# Angelo_Dual_Filter_MAIN_v1.net
KiCad netlist of a schematic drawn in EAGLE
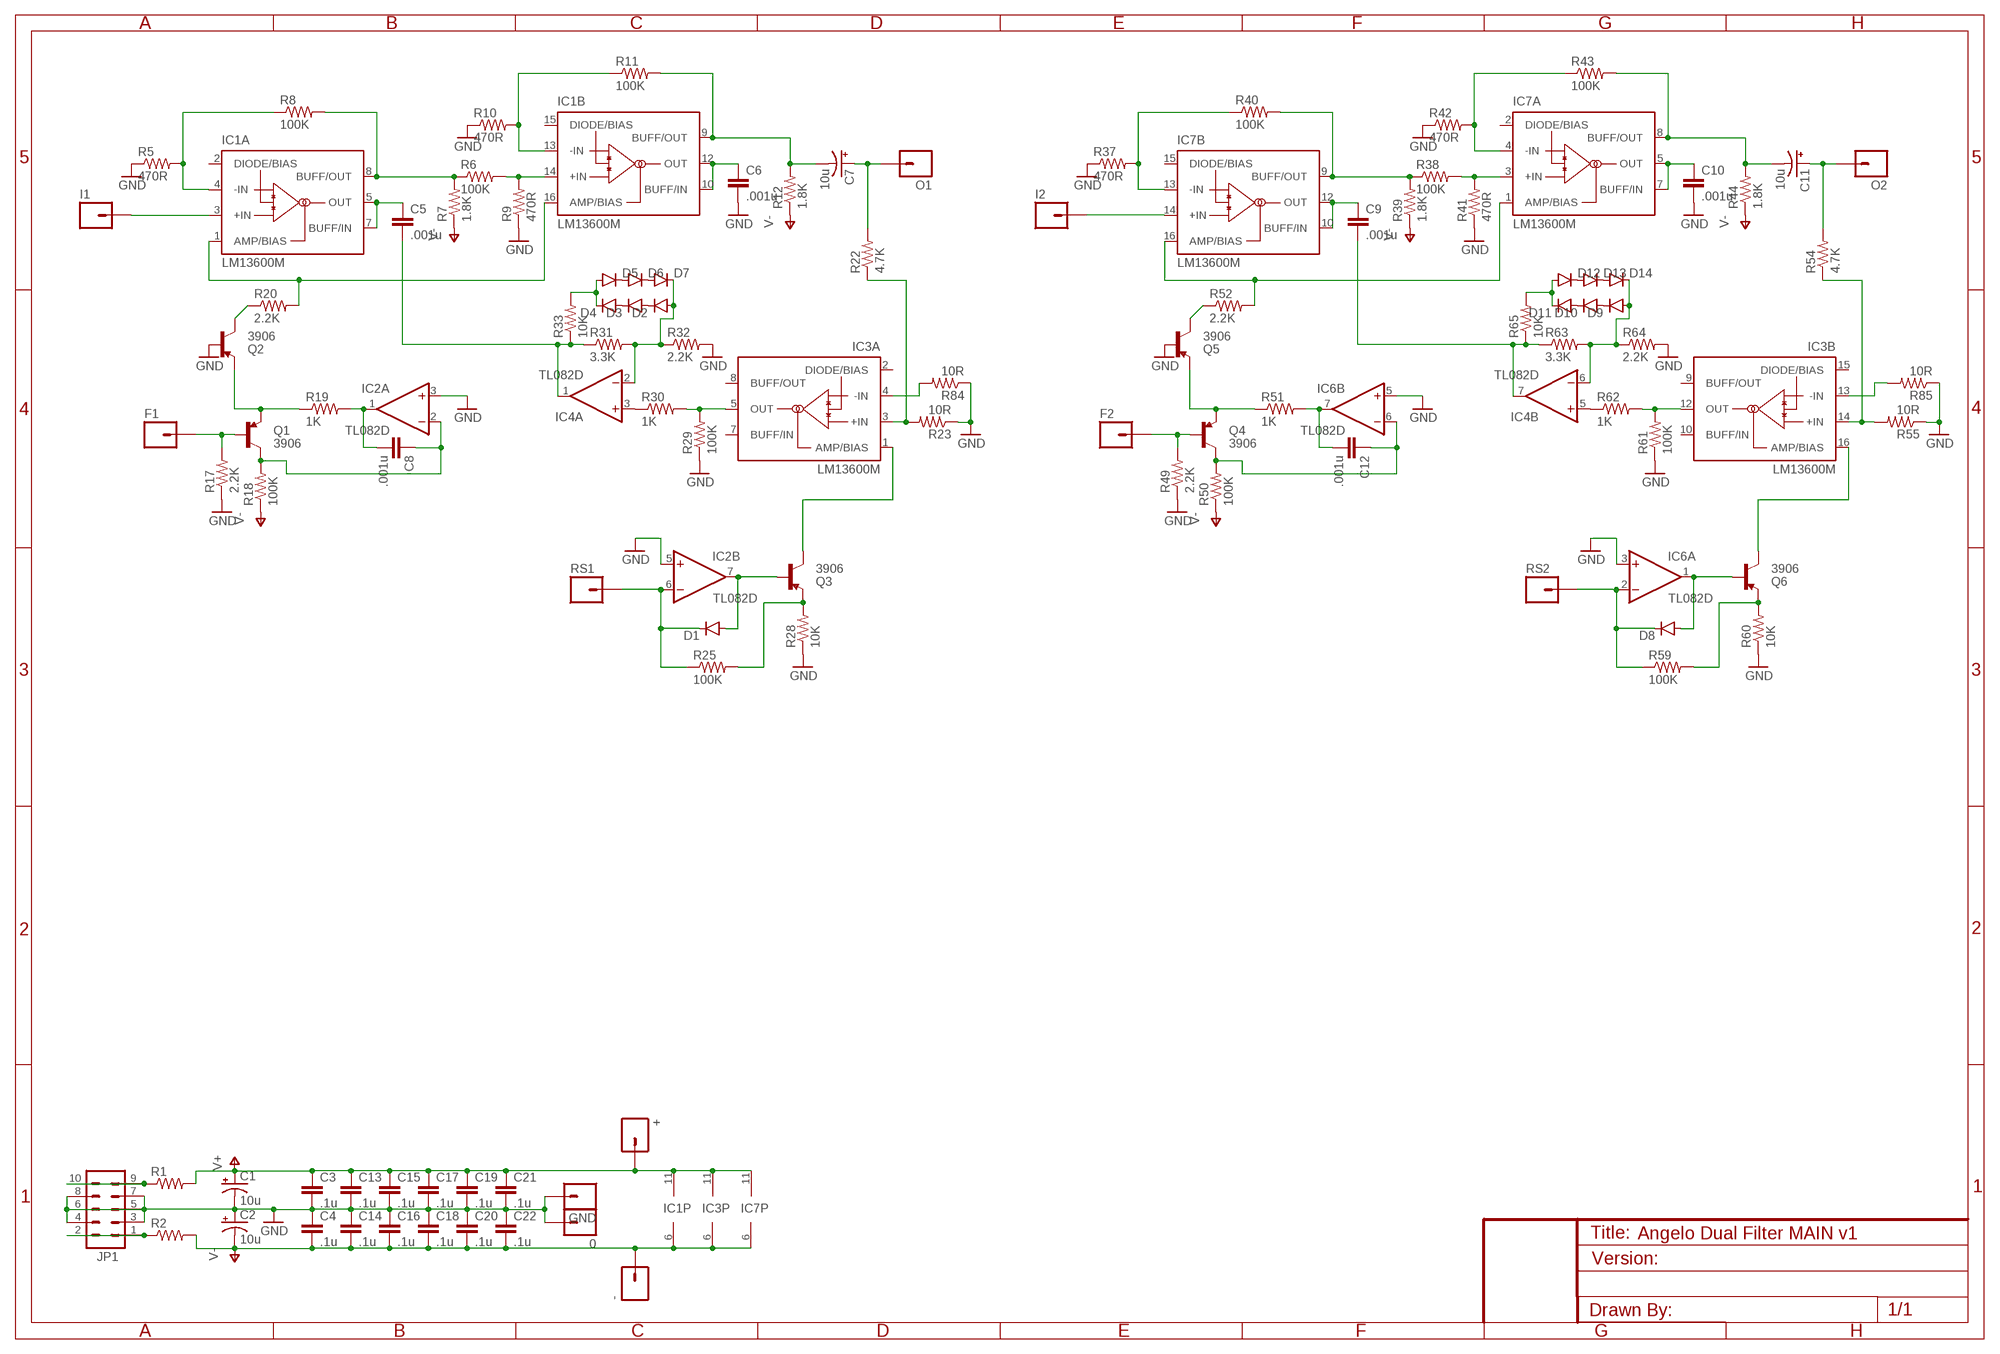
[diagram p0: schematic, sheet 1]

(export (version "E")
  (design (tool "Eeschema 10.0.6"))
  (components
    (comp (ref "+")
      (value "M01PTH")
      (footprint "eagle-import:1X01")
      (libsource (lib "eagle-import") (part "M01PTH"))
    )
    (comp (ref "-")
      (value "M01PTH")
      (footprint "eagle-import:1X01")
      (libsource (lib "eagle-import") (part "M01PTH"))
    )
    (comp (ref "0")
      (value "M01PTH")
      (footprint "eagle-import:1X01")
      (libsource (lib "eagle-import") (part "M01PTH"))
    )
    (comp (ref "C1")
      (value "10u")
      (footprint "eagle-import:CPOL-RADIAL-10UF-25V")
      (libsource (lib "eagle-import") (part "CAP_POLPTH2"))
    )
    (comp (ref "C2")
      (value "10u")
      (footprint "eagle-import:CPOL-RADIAL-10UF-25V")
      (libsource (lib "eagle-import") (part "CAP_POLPTH2"))
    )
    (comp (ref "C3")
      (value ".1u")
      (footprint "eagle-import:0805")
      (libsource (lib "eagle-import") (part "CAP0805"))
    )
    (comp (ref "C4")
      (value ".1u")
      (footprint "eagle-import:0805")
      (libsource (lib "eagle-import") (part "CAP0805"))
    )
    (comp (ref "C5")
      (value ".001u")
      (footprint "eagle-import:C5B2.5")
      (libsource (lib "eagle-import") (part "C5/2.5"))
    )
    (comp (ref "C6")
      (value ".001u")
      (footprint "eagle-import:C5B2.5")
      (libsource (lib "eagle-import") (part "C5/2.5"))
    )
    (comp (ref "C7")
      (value "10u")
      (footprint "eagle-import:CPOL-RADIAL-10UF-25V")
      (libsource (lib "eagle-import") (part "CAP_POLPTH2"))
    )
    (comp (ref "C8")
      (value ".001u")
      (footprint "eagle-import:0805")
      (libsource (lib "eagle-import") (part "CAP0805"))
    )
    (comp (ref "C9")
      (value ".001u")
      (footprint "eagle-import:C5B2.5")
      (libsource (lib "eagle-import") (part "C5/2.5"))
    )
    (comp (ref "C10")
      (value ".001u")
      (footprint "eagle-import:C5B2.5")
      (libsource (lib "eagle-import") (part "C5/2.5"))
    )
    (comp (ref "C11")
      (value "10u")
      (footprint "eagle-import:CPOL-RADIAL-10UF-25V")
      (libsource (lib "eagle-import") (part "CAP_POLPTH2"))
    )
    (comp (ref "C12")
      (value ".001u")
      (footprint "eagle-import:0805")
      (libsource (lib "eagle-import") (part "CAP0805"))
    )
    (comp (ref "C13")
      (value ".1u")
      (footprint "eagle-import:0805")
      (libsource (lib "eagle-import") (part "CAP0805"))
    )
    (comp (ref "C14")
      (value ".1u")
      (footprint "eagle-import:0805")
      (libsource (lib "eagle-import") (part "CAP0805"))
    )
    (comp (ref "C15")
      (value ".1u")
      (footprint "eagle-import:0805")
      (libsource (lib "eagle-import") (part "CAP0805"))
    )
    (comp (ref "C16")
      (value ".1u")
      (footprint "eagle-import:0805")
      (libsource (lib "eagle-import") (part "CAP0805"))
    )
    (comp (ref "C17")
      (value ".1u")
      (footprint "eagle-import:0805")
      (libsource (lib "eagle-import") (part "CAP0805"))
    )
    (comp (ref "C18")
      (value ".1u")
      (footprint "eagle-import:0805")
      (libsource (lib "eagle-import") (part "CAP0805"))
    )
    (comp (ref "C19")
      (value ".1u")
      (footprint "eagle-import:0805")
      (libsource (lib "eagle-import") (part "CAP0805"))
    )
    (comp (ref "C20")
      (value ".1u")
      (footprint "eagle-import:0805")
      (libsource (lib "eagle-import") (part "CAP0805"))
    )
    (comp (ref "C21")
      (value ".1u")
      (footprint "eagle-import:0805")
      (libsource (lib "eagle-import") (part "CAP0805"))
    )
    (comp (ref "C22")
      (value ".1u")
      (footprint "eagle-import:0805")
      (libsource (lib "eagle-import") (part "CAP0805"))
    )
    (comp (ref "D1")
      (value "DIODESOD123")
      (footprint "eagle-import:SOD-123")
      (libsource (lib "eagle-import") (part "DIODESOD123"))
    )
    (comp (ref "D2")
      (value "DIODESOD123")
      (footprint "eagle-import:SOD-123")
      (libsource (lib "eagle-import") (part "DIODESOD123"))
    )
    (comp (ref "D3")
      (value "DIODESOD123")
      (footprint "eagle-import:SOD-123")
      (libsource (lib "eagle-import") (part "DIODESOD123"))
    )
    (comp (ref "D4")
      (value "DIODESOD123")
      (footprint "eagle-import:SOD-123")
      (libsource (lib "eagle-import") (part "DIODESOD123"))
    )
    (comp (ref "D5")
      (value "DIODESOD123")
      (footprint "eagle-import:SOD-123")
      (libsource (lib "eagle-import") (part "DIODESOD123"))
    )
    (comp (ref "D6")
      (value "DIODESOD123")
      (footprint "eagle-import:SOD-123")
      (libsource (lib "eagle-import") (part "DIODESOD123"))
    )
    (comp (ref "D7")
      (value "DIODESOD123")
      (footprint "eagle-import:SOD-123")
      (libsource (lib "eagle-import") (part "DIODESOD123"))
    )
    (comp (ref "D8")
      (value "DIODESOD123")
      (footprint "eagle-import:SOD-123")
      (libsource (lib "eagle-import") (part "DIODESOD123"))
    )
    (comp (ref "D9")
      (value "DIODESOD123")
      (footprint "eagle-import:SOD-123")
      (libsource (lib "eagle-import") (part "DIODESOD123"))
    )
    (comp (ref "D10")
      (value "DIODESOD123")
      (footprint "eagle-import:SOD-123")
      (libsource (lib "eagle-import") (part "DIODESOD123"))
    )
    (comp (ref "D11")
      (value "DIODESOD123")
      (footprint "eagle-import:SOD-123")
      (libsource (lib "eagle-import") (part "DIODESOD123"))
    )
    (comp (ref "D12")
      (value "DIODESOD123")
      (footprint "eagle-import:SOD-123")
      (libsource (lib "eagle-import") (part "DIODESOD123"))
    )
    (comp (ref "D13")
      (value "DIODESOD123")
      (footprint "eagle-import:SOD-123")
      (libsource (lib "eagle-import") (part "DIODESOD123"))
    )
    (comp (ref "D14")
      (value "DIODESOD123")
      (footprint "eagle-import:SOD-123")
      (libsource (lib "eagle-import") (part "DIODESOD123"))
    )
    (comp (ref "F1")
      (value "M01PTH")
      (footprint "eagle-import:1X01")
      (libsource (lib "eagle-import") (part "M01PTH"))
    )
    (comp (ref "F2")
      (value "M01PTH")
      (footprint "eagle-import:1X01")
      (libsource (lib "eagle-import") (part "M01PTH"))
    )
    (comp (ref "GND")
      (value "M01PTH")
      (footprint "eagle-import:1X01")
      (libsource (lib "eagle-import") (part "M01PTH"))
    )
    (comp (ref "I1")
      (value "M01PTH")
      (footprint "eagle-import:1X01")
      (libsource (lib "eagle-import") (part "M01PTH"))
    )
    (comp (ref "I2")
      (value "M01PTH")
      (footprint "eagle-import:1X01")
      (libsource (lib "eagle-import") (part "M01PTH"))
    )
    (comp (ref "IC1")
      (value "LM13600M")
      (footprint "eagle-import:SO16")
      (libsource (lib "eagle-import") (part "LM13600M"))
    )
    (comp (ref "IC2")
      (value "TL082D")
      (footprint "eagle-import:SO08")
      (libsource (lib "eagle-import") (part "TL082D"))
    )
    (comp (ref "IC3")
      (value "LM13600M")
      (footprint "eagle-import:SO16")
      (libsource (lib "eagle-import") (part "LM13600M"))
    )
    (comp (ref "IC4")
      (value "TL082D")
      (footprint "eagle-import:SO08")
      (libsource (lib "eagle-import") (part "TL082D"))
    )
    (comp (ref "IC6")
      (value "TL082D")
      (footprint "eagle-import:SO08")
      (libsource (lib "eagle-import") (part "TL082D"))
    )
    (comp (ref "IC7")
      (value "LM13600M")
      (footprint "eagle-import:SO16")
      (libsource (lib "eagle-import") (part "LM13600M"))
    )
    (comp (ref "JP1")
      (value "M05X2PTH")
      (footprint "eagle-import:AVR_ICSP")
      (libsource (lib "eagle-import") (part "M05X2PTH"))
    )
    (comp (ref "O1")
      (value "M01PTH")
      (footprint "eagle-import:1X01")
      (libsource (lib "eagle-import") (part "M01PTH"))
    )
    (comp (ref "O2")
      (value "M01PTH")
      (footprint "eagle-import:1X01")
      (libsource (lib "eagle-import") (part "M01PTH"))
    )
    (comp (ref "Q1")
      (value "3906")
      (footprint "eagle-import:SOT23-3")
      (libsource (lib "eagle-import") (part "TRANSISTOR_PNPPMBT3906"))
    )
    (comp (ref "Q2")
      (value "3906")
      (footprint "eagle-import:SOT23-3")
      (libsource (lib "eagle-import") (part "TRANSISTOR_PNPPMBT3906"))
    )
    (comp (ref "Q3")
      (value "3906")
      (footprint "eagle-import:SOT23-3")
      (libsource (lib "eagle-import") (part "TRANSISTOR_PNPPMBT3906"))
    )
    (comp (ref "Q4")
      (value "3906")
      (footprint "eagle-import:SOT23-3")
      (libsource (lib "eagle-import") (part "TRANSISTOR_PNPPMBT3906"))
    )
    (comp (ref "Q5")
      (value "3906")
      (footprint "eagle-import:SOT23-3")
      (libsource (lib "eagle-import") (part "TRANSISTOR_PNPPMBT3906"))
    )
    (comp (ref "Q6")
      (value "3906")
      (footprint "eagle-import:SOT23-3")
      (libsource (lib "eagle-import") (part "TRANSISTOR_PNPPMBT3906"))
    )
    (comp (ref "R1")
      (value "RESISTOR0805-RES")
      (footprint "eagle-import:0805")
      (libsource (lib "eagle-import") (part "RESISTOR0805-RES"))
    )
    (comp (ref "R2")
      (value "RESISTOR0805-RES")
      (footprint "eagle-import:0805")
      (libsource (lib "eagle-import") (part "RESISTOR0805-RES"))
    )
    (comp (ref "R5")
      (value "470R")
      (footprint "eagle-import:0805")
      (libsource (lib "eagle-import") (part "RESISTOR0805-RES"))
    )
    (comp (ref "R6")
      (value "100K")
      (footprint "eagle-import:0805")
      (libsource (lib "eagle-import") (part "RESISTOR0805-RES"))
    )
    (comp (ref "R7")
      (value "1.8K")
      (footprint "eagle-import:0805")
      (libsource (lib "eagle-import") (part "RESISTOR0805-RES"))
    )
    (comp (ref "R8")
      (value "100K")
      (footprint "eagle-import:0805")
      (libsource (lib "eagle-import") (part "RESISTOR0805-RES"))
    )
    (comp (ref "R9")
      (value "470R")
      (footprint "eagle-import:0805")
      (libsource (lib "eagle-import") (part "RESISTOR0805-RES"))
    )
    (comp (ref "R10")
      (value "470R")
      (footprint "eagle-import:0805")
      (libsource (lib "eagle-import") (part "RESISTOR0805-RES"))
    )
    (comp (ref "R11")
      (value "100K")
      (footprint "eagle-import:0805")
      (libsource (lib "eagle-import") (part "RESISTOR0805-RES"))
    )
    (comp (ref "R12")
      (value "1.8K")
      (footprint "eagle-import:0805")
      (libsource (lib "eagle-import") (part "RESISTOR0805-RES"))
    )
    (comp (ref "R17")
      (value "2.2K")
      (footprint "eagle-import:0805")
      (libsource (lib "eagle-import") (part "RESISTOR0805-RES"))
    )
    (comp (ref "R18")
      (value "100K")
      (footprint "eagle-import:0805")
      (libsource (lib "eagle-import") (part "RESISTOR0805-RES"))
    )
    (comp (ref "R19")
      (value "1K")
      (footprint "eagle-import:0805")
      (libsource (lib "eagle-import") (part "RESISTOR0805-RES"))
    )
    (comp (ref "R20")
      (value "2.2K")
      (footprint "eagle-import:0805")
      (libsource (lib "eagle-import") (part "RESISTOR0805-RES"))
    )
    (comp (ref "R22")
      (value "4.7K")
      (footprint "eagle-import:0805")
      (libsource (lib "eagle-import") (part "RESISTOR0805-RES"))
    )
    (comp (ref "R23")
      (value "10R")
      (footprint "eagle-import:0805")
      (libsource (lib "eagle-import") (part "RESISTOR0805-RES"))
    )
    (comp (ref "R25")
      (value "100K")
      (footprint "eagle-import:0805")
      (libsource (lib "eagle-import") (part "RESISTOR0805-RES"))
    )
    (comp (ref "R28")
      (value "10K")
      (footprint "eagle-import:0805")
      (libsource (lib "eagle-import") (part "RESISTOR0805-RES"))
    )
    (comp (ref "R29")
      (value "100K")
      (footprint "eagle-import:0805")
      (libsource (lib "eagle-import") (part "RESISTOR0805-RES"))
    )
    (comp (ref "R30")
      (value "1K")
      (footprint "eagle-import:0805")
      (libsource (lib "eagle-import") (part "RESISTOR0805-RES"))
    )
    (comp (ref "R31")
      (value "3.3K")
      (footprint "eagle-import:0805")
      (libsource (lib "eagle-import") (part "RESISTOR0805-RES"))
    )
    (comp (ref "R32")
      (value "2.2K")
      (footprint "eagle-import:0805")
      (libsource (lib "eagle-import") (part "RESISTOR0805-RES"))
    )
    (comp (ref "R33")
      (value "10K")
      (footprint "eagle-import:0805")
      (libsource (lib "eagle-import") (part "RESISTOR0805-RES"))
    )
    (comp (ref "R37")
      (value "470R")
      (footprint "eagle-import:0805")
      (libsource (lib "eagle-import") (part "RESISTOR0805-RES"))
    )
    (comp (ref "R38")
      (value "100K")
      (footprint "eagle-import:0805")
      (libsource (lib "eagle-import") (part "RESISTOR0805-RES"))
    )
    (comp (ref "R39")
      (value "1.8K")
      (footprint "eagle-import:0805")
      (libsource (lib "eagle-import") (part "RESISTOR0805-RES"))
    )
    (comp (ref "R40")
      (value "100K")
      (footprint "eagle-import:0805")
      (libsource (lib "eagle-import") (part "RESISTOR0805-RES"))
    )
    (comp (ref "R41")
      (value "470R")
      (footprint "eagle-import:0805")
      (libsource (lib "eagle-import") (part "RESISTOR0805-RES"))
    )
    (comp (ref "R42")
      (value "470R")
      (footprint "eagle-import:0805")
      (libsource (lib "eagle-import") (part "RESISTOR0805-RES"))
    )
    (comp (ref "R43")
      (value "100K")
      (footprint "eagle-import:0805")
      (libsource (lib "eagle-import") (part "RESISTOR0805-RES"))
    )
    (comp (ref "R44")
      (value "1.8K")
      (footprint "eagle-import:0805")
      (libsource (lib "eagle-import") (part "RESISTOR0805-RES"))
    )
    (comp (ref "R49")
      (value "2.2K")
      (footprint "eagle-import:0805")
      (libsource (lib "eagle-import") (part "RESISTOR0805-RES"))
    )
    (comp (ref "R50")
      (value "100K")
      (footprint "eagle-import:0805")
      (libsource (lib "eagle-import") (part "RESISTOR0805-RES"))
    )
    (comp (ref "R51")
      (value "1K")
      (footprint "eagle-import:0805")
      (libsource (lib "eagle-import") (part "RESISTOR0805-RES"))
    )
    (comp (ref "R52")
      (value "2.2K")
      (footprint "eagle-import:0805")
      (libsource (lib "eagle-import") (part "RESISTOR0805-RES"))
    )
    (comp (ref "R54")
      (value "4.7K")
      (footprint "eagle-import:0805")
      (libsource (lib "eagle-import") (part "RESISTOR0805-RES"))
    )
    (comp (ref "R55")
      (value "10R")
      (footprint "eagle-import:0805")
      (libsource (lib "eagle-import") (part "RESISTOR0805-RES"))
    )
    (comp (ref "R59")
      (value "100K")
      (footprint "eagle-import:0805")
      (libsource (lib "eagle-import") (part "RESISTOR0805-RES"))
    )
    (comp (ref "R60")
      (value "10K")
      (footprint "eagle-import:0805")
      (libsource (lib "eagle-import") (part "RESISTOR0805-RES"))
    )
    (comp (ref "R61")
      (value "100K")
      (footprint "eagle-import:0805")
      (libsource (lib "eagle-import") (part "RESISTOR0805-RES"))
    )
    (comp (ref "R62")
      (value "1K")
      (footprint "eagle-import:0805")
      (libsource (lib "eagle-import") (part "RESISTOR0805-RES"))
    )
    (comp (ref "R63")
      (value "3.3K")
      (footprint "eagle-import:0805")
      (libsource (lib "eagle-import") (part "RESISTOR0805-RES"))
    )
    (comp (ref "R64")
      (value "2.2K")
      (footprint "eagle-import:0805")
      (libsource (lib "eagle-import") (part "RESISTOR0805-RES"))
    )
    (comp (ref "R65")
      (value "10K")
      (footprint "eagle-import:0805")
      (libsource (lib "eagle-import") (part "RESISTOR0805-RES"))
    )
    (comp (ref "R84")
      (value "10R")
      (footprint "eagle-import:0805")
      (libsource (lib "eagle-import") (part "RESISTOR0805-RES"))
    )
    (comp (ref "R85")
      (value "10R")
      (footprint "eagle-import:0805")
      (libsource (lib "eagle-import") (part "RESISTOR0805-RES"))
    )
    (comp (ref "RS1")
      (value "M01PTH")
      (footprint "eagle-import:1X01")
      (libsource (lib "eagle-import") (part "M01PTH"))
    )
    (comp (ref "RS2")
      (value "M01PTH")
      (footprint "eagle-import:1X01")
      (libsource (lib "eagle-import") (part "M01PTH"))
    )
  )
  (nets
    (net (code "1") (name "GND") (class "Default")
      (node (ref "0") (pin "1") (pinfunction "1_1") (pintype "passive"))
      (node (ref "C1") (pin "2") (pinfunction "-_2") (pintype "passive"))
      (node (ref "C10") (pin "2") (pinfunction "2_2") (pintype "passive"))
      (node (ref "C13") (pin "2") (pinfunction "2_2") (pintype "passive"))
      (node (ref "C14") (pin "1") (pinfunction "1_1") (pintype "passive"))
      (node (ref "C15") (pin "2") (pinfunction "2_2") (pintype "passive"))
      (node (ref "C16") (pin "1") (pinfunction "1_1") (pintype "passive"))
      (node (ref "C17") (pin "2") (pinfunction "2_2") (pintype "passive"))
      (node (ref "C18") (pin "1") (pinfunction "1_1") (pintype "passive"))
      (node (ref "C19") (pin "2") (pinfunction "2_2") (pintype "passive"))
      (node (ref "C2") (pin "1") (pinfunction "+_1") (pintype "passive"))
      (node (ref "C20") (pin "1") (pinfunction "1_1") (pintype "passive"))
      (node (ref "C21") (pin "2") (pinfunction "2_2") (pintype "passive"))
      (node (ref "C22") (pin "1") (pinfunction "1_1") (pintype "passive"))
      (node (ref "C3") (pin "2") (pinfunction "2_2") (pintype "passive"))
      (node (ref "C4") (pin "1") (pinfunction "1_1") (pintype "passive"))
      (node (ref "C6") (pin "2") (pinfunction "2_2") (pintype "passive"))
      (node (ref "GND") (pin "1") (pinfunction "1_1") (pintype "passive"))
      (node (ref "IC2") (pin "3") (pinfunction "+IN_3") (pintype "input"))
      (node (ref "IC2") (pin "5") (pinfunction "+IN_5") (pintype "input"))
      (node (ref "IC6") (pin "3") (pinfunction "+IN_3") (pintype "input"))
      (node (ref "IC6") (pin "5") (pinfunction "+IN_5") (pintype "input"))
      (node (ref "JP1") (pin "3") (pinfunction "3_3") (pintype "passive"))
      (node (ref "JP1") (pin "4") (pinfunction "4_4") (pintype "passive"))
      (node (ref "JP1") (pin "5") (pinfunction "5_5") (pintype "passive"))
      (node (ref "JP1") (pin "6") (pinfunction "6_6") (pintype "passive"))
      (node (ref "JP1") (pin "7") (pinfunction "7_7") (pintype "passive"))
      (node (ref "JP1") (pin "8") (pinfunction "8_8") (pintype "passive"))
      (node (ref "Q2") (pin "1") (pinfunction "B_1") (pintype "passive"))
      (node (ref "Q5") (pin "1") (pinfunction "B_1") (pintype "passive"))
      (node (ref "R10") (pin "1") (pinfunction "1_1") (pintype "passive"))
      (node (ref "R17") (pin "1") (pinfunction "1_1") (pintype "passive"))
      (node (ref "R23") (pin "1") (pinfunction "1_1") (pintype "passive"))
      (node (ref "R28") (pin "1") (pinfunction "1_1") (pintype "passive"))
      (node (ref "R29") (pin "1") (pinfunction "1_1") (pintype "passive"))
      (node (ref "R32") (pin "2") (pinfunction "2_2") (pintype "passive"))
      (node (ref "R37") (pin "1") (pinfunction "1_1") (pintype "passive"))
      (node (ref "R41") (pin "1") (pinfunction "1_1") (pintype "passive"))
      (node (ref "R42") (pin "1") (pinfunction "1_1") (pintype "passive"))
      (node (ref "R49") (pin "1") (pinfunction "1_1") (pintype "passive"))
      (node (ref "R5") (pin "1") (pinfunction "1_1") (pintype "passive"))
      (node (ref "R55") (pin "1") (pinfunction "1_1") (pintype "passive"))
      (node (ref "R60") (pin "1") (pinfunction "1_1") (pintype "passive"))
      (node (ref "R61") (pin "1") (pinfunction "1_1") (pintype "passive"))
      (node (ref "R64") (pin "2") (pinfunction "2_2") (pintype "passive"))
      (node (ref "R84") (pin "1") (pinfunction "1_1") (pintype "passive"))
      (node (ref "R85") (pin "1") (pinfunction "1_1") (pintype "passive"))
      (node (ref "R9") (pin "1") (pinfunction "1_1") (pintype "passive"))
    )
    (net (code "2") (name "Net-(C7-+)") (class "Default")
      (node (ref "C7") (pin "1") (pinfunction "+_1") (pintype "passive"))
      (node (ref "O1") (pin "1") (pinfunction "1_1") (pintype "passive"))
      (node (ref "R22") (pin "2") (pinfunction "2_2") (pintype "passive"))
    )
    (net (code "3") (name "Net-(C7--)") (class "Default")
      (node (ref "C7") (pin "2") (pinfunction "-_2") (pintype "passive"))
      (node (ref "IC1") (pin "9") (pinfunction "BUFF/OUT_9") (pintype "output"))
      (node (ref "R11") (pin "2") (pinfunction "2_2") (pintype "passive"))
      (node (ref "R12") (pin "2") (pinfunction "2_2") (pintype "passive"))
    )
    (net (code "4") (name "Net-(C11-+)") (class "Default")
      (node (ref "C11") (pin "1") (pinfunction "+_1") (pintype "passive"))
      (node (ref "O2") (pin "1") (pinfunction "1_1") (pintype "passive"))
      (node (ref "R54") (pin "2") (pinfunction "2_2") (pintype "passive"))
    )
    (net (code "5") (name "Net-(C11--)") (class "Default")
      (node (ref "C11") (pin "2") (pinfunction "-_2") (pintype "passive"))
      (node (ref "IC7") (pin "8") (pinfunction "BUFF/OUT_8") (pintype "output"))
      (node (ref "R43") (pin "2") (pinfunction "2_2") (pintype "passive"))
      (node (ref "R44") (pin "2") (pinfunction "2_2") (pintype "passive"))
    )
    (net (code "6") (name "Net-(D2-PadC)") (class "Default")
      (node (ref "D2") (pin "C") (pinfunction "C_C") (pintype "passive"))
      (node (ref "D3") (pin "A") (pinfunction "A_A") (pintype "passive"))
    )
    (net (code "7") (name "Net-(D3-PadC)") (class "Default")
      (node (ref "D3") (pin "C") (pinfunction "C_C") (pintype "passive"))
      (node (ref "D4") (pin "A") (pinfunction "A_A") (pintype "passive"))
    )
    (net (code "8") (name "Net-(D4-PadC)") (class "Default")
      (node (ref "D4") (pin "C") (pinfunction "C_C") (pintype "passive"))
      (node (ref "D5") (pin "A") (pinfunction "A_A") (pintype "passive"))
      (node (ref "R33") (pin "2") (pinfunction "2_2") (pintype "passive"))
    )
    (net (code "9") (name "Net-(D5-PadC)") (class "Default")
      (node (ref "D5") (pin "C") (pinfunction "C_C") (pintype "passive"))
      (node (ref "D6") (pin "A") (pinfunction "A_A") (pintype "passive"))
    )
    (net (code "10") (name "Net-(D6-PadC)") (class "Default")
      (node (ref "D6") (pin "C") (pinfunction "C_C") (pintype "passive"))
      (node (ref "D7") (pin "A") (pinfunction "A_A") (pintype "passive"))
    )
    (net (code "11") (name "Net-(D10-PadA)") (class "Default")
      (node (ref "D10") (pin "A") (pinfunction "A_A") (pintype "passive"))
      (node (ref "D9") (pin "C") (pinfunction "C_C") (pintype "passive"))
    )
    (net (code "12") (name "Net-(D10-PadC)") (class "Default")
      (node (ref "D10") (pin "C") (pinfunction "C_C") (pintype "passive"))
      (node (ref "D11") (pin "A") (pinfunction "A_A") (pintype "passive"))
    )
    (net (code "13") (name "Net-(D11-PadC)") (class "Default")
      (node (ref "D11") (pin "C") (pinfunction "C_C") (pintype "passive"))
      (node (ref "D12") (pin "A") (pinfunction "A_A") (pintype "passive"))
      (node (ref "R65") (pin "2") (pinfunction "2_2") (pintype "passive"))
    )
    (net (code "14") (name "Net-(D12-PadC)") (class "Default")
      (node (ref "D12") (pin "C") (pinfunction "C_C") (pintype "passive"))
      (node (ref "D13") (pin "A") (pinfunction "A_A") (pintype "passive"))
    )
    (net (code "15") (name "Net-(D13-PadC)") (class "Default")
      (node (ref "D13") (pin "C") (pinfunction "C_C") (pintype "passive"))
      (node (ref "D14") (pin "A") (pinfunction "A_A") (pintype "passive"))
    )
    (net (code "16") (name "Net-(IC1A-+IN)") (class "Default")
      (node (ref "I1") (pin "1") (pinfunction "1_1") (pintype "passive"))
      (node (ref "IC1") (pin "3") (pinfunction "+IN_3") (pintype "input"))
    )
    (net (code "17") (name "Net-(IC1A--IN)") (class "Default")
      (node (ref "IC1") (pin "4") (pinfunction "-IN_4") (pintype "input"))
      (node (ref "R5") (pin "2") (pinfunction "2_2") (pintype "passive"))
      (node (ref "R8") (pin "1") (pinfunction "1_1") (pintype "passive"))
    )
    (net (code "18") (name "Net-(IC1A-AMP{slash}BIAS)") (class "Default")
      (node (ref "IC1") (pin "1") (pinfunction "AMP/BIAS_1") (pintype "passive"))
      (node (ref "IC1") (pin "16") (pinfunction "AMP/BIAS_16") (pintype "passive"))
      (node (ref "R20") (pin "2") (pinfunction "2_2") (pintype "passive"))
    )
    (net (code "19") (name "Net-(IC1A-BUFF{slash}IN)") (class "Default")
      (node (ref "C5") (pin "1") (pinfunction "1_1") (pintype "passive"))
      (node (ref "IC1") (pin "5") (pinfunction "OUT_5") (pintype "output"))
      (node (ref "IC1") (pin "7") (pinfunction "BUFF/IN_7") (pintype "input"))
    )
    (net (code "20") (name "Net-(IC1A-BUFF{slash}OUT)") (class "Default")
      (node (ref "IC1") (pin "8") (pinfunction "BUFF/OUT_8") (pintype "output"))
      (node (ref "R6") (pin "1") (pinfunction "1_1") (pintype "passive"))
      (node (ref "R7") (pin "2") (pinfunction "2_2") (pintype "passive"))
      (node (ref "R8") (pin "2") (pinfunction "2_2") (pintype "passive"))
    )
    (net (code "21") (name "Net-(IC1B-+IN)") (class "Default")
      (node (ref "IC1") (pin "14") (pinfunction "+IN_14") (pintype "input"))
      (node (ref "R6") (pin "2") (pinfunction "2_2") (pintype "passive"))
      (node (ref "R9") (pin "2") (pinfunction "2_2") (pintype "passive"))
    )
    (net (code "22") (name "Net-(IC1B--IN)") (class "Default")
      (node (ref "IC1") (pin "13") (pinfunction "-IN_13") (pintype "input"))
      (node (ref "R10") (pin "2") (pinfunction "2_2") (pintype "passive"))
      (node (ref "R11") (pin "1") (pinfunction "1_1") (pintype "passive"))
    )
    (net (code "23") (name "Net-(IC1B-BUFF{slash}IN)") (class "Default")
      (node (ref "C6") (pin "1") (pinfunction "1_1") (pintype "passive"))
      (node (ref "IC1") (pin "10") (pinfunction "BUFF/IN_10") (pintype "input"))
      (node (ref "IC1") (pin "12") (pinfunction "OUT_12") (pintype "output"))
    )
    (net (code "24") (name "Net-(IC2A--IN)") (class "Default")
      (node (ref "C8") (pin "1") (pinfunction "1_1") (pintype "passive"))
      (node (ref "IC2") (pin "2") (pinfunction "-IN_2") (pintype "input"))
      (node (ref "Q1") (pin "3") (pinfunction "C_3") (pintype "passive"))
      (node (ref "R18") (pin "2") (pinfunction "2_2") (pintype "passive"))
    )
    (net (code "25") (name "Net-(IC2A-OUT)") (class "Default")
      (node (ref "C8") (pin "2") (pinfunction "2_2") (pintype "passive"))
      (node (ref "IC2") (pin "1") (pinfunction "OUT_1") (pintype "output"))
      (node (ref "R19") (pin "2") (pinfunction "2_2") (pintype "passive"))
    )
    (net (code "26") (name "Net-(IC2B--IN)") (class "Default")
      (node (ref "D1") (pin "C") (pinfunction "C_C") (pintype "passive"))
      (node (ref "IC2") (pin "6") (pinfunction "-IN_6") (pintype "input"))
      (node (ref "R25") (pin "1") (pinfunction "1_1") (pintype "passive"))
      (node (ref "RS1") (pin "1") (pinfunction "1_1") (pintype "passive"))
    )
    (net (code "27") (name "Net-(IC2B-OUT)") (class "Default")
      (node (ref "D1") (pin "A") (pinfunction "A_A") (pintype "passive"))
      (node (ref "IC2") (pin "7") (pinfunction "OUT_7") (pintype "output"))
      (node (ref "Q3") (pin "1") (pinfunction "B_1") (pintype "passive"))
    )
    (net (code "28") (name "Net-(IC3A-+IN)") (class "Default")
      (node (ref "IC3") (pin "3") (pinfunction "+IN_3") (pintype "input"))
      (node (ref "R22") (pin "1") (pinfunction "1_1") (pintype "passive"))
      (node (ref "R23") (pin "2") (pinfunction "2_2") (pintype "passive"))
    )
    (net (code "29") (name "Net-(IC3A--IN)") (class "Default")
      (node (ref "IC3") (pin "4") (pinfunction "-IN_4") (pintype "input"))
      (node (ref "R84") (pin "2") (pinfunction "2_2") (pintype "passive"))
    )
    (net (code "30") (name "Net-(IC3A-AMP{slash}BIAS)") (class "Default")
      (node (ref "IC3") (pin "1") (pinfunction "AMP/BIAS_1") (pintype "passive"))
      (node (ref "Q3") (pin "3") (pinfunction "C_3") (pintype "passive"))
    )
    (net (code "31") (name "Net-(IC3A-OUT)") (class "Default")
      (node (ref "IC3") (pin "5") (pinfunction "OUT_5") (pintype "output"))
      (node (ref "R29") (pin "2") (pinfunction "2_2") (pintype "passive"))
      (node (ref "R30") (pin "2") (pinfunction "2_2") (pintype "passive"))
    )
    (net (code "32") (name "Net-(IC3B-+IN)") (class "Default")
      (node (ref "IC3") (pin "14") (pinfunction "+IN_14") (pintype "input"))
      (node (ref "R54") (pin "1") (pinfunction "1_1") (pintype "passive"))
      (node (ref "R55") (pin "2") (pinfunction "2_2") (pintype "passive"))
    )
    (net (code "33") (name "Net-(IC3B--IN)") (class "Default")
      (node (ref "IC3") (pin "13") (pinfunction "-IN_13") (pintype "input"))
      (node (ref "R85") (pin "2") (pinfunction "2_2") (pintype "passive"))
    )
    (net (code "34") (name "Net-(IC3B-AMP{slash}BIAS)") (class "Default")
      (node (ref "IC3") (pin "16") (pinfunction "AMP/BIAS_16") (pintype "passive"))
      (node (ref "Q6") (pin "3") (pinfunction "C_3") (pintype "passive"))
    )
    (net (code "35") (name "Net-(IC3B-OUT)") (class "Default")
      (node (ref "IC3") (pin "12") (pinfunction "OUT_12") (pintype "output"))
      (node (ref "R61") (pin "2") (pinfunction "2_2") (pintype "passive"))
      (node (ref "R62") (pin "2") (pinfunction "2_2") (pintype "passive"))
    )
    (net (code "36") (name "Net-(IC4A-+IN)") (class "Default")
      (node (ref "IC4") (pin "3") (pinfunction "+IN_3") (pintype "input"))
      (node (ref "R30") (pin "1") (pinfunction "1_1") (pintype "passive"))
    )
    (net (code "37") (name "Net-(IC4A--IN)") (class "Default")
      (node (ref "D2") (pin "A") (pinfunction "A_A") (pintype "passive"))
      (node (ref "D7") (pin "C") (pinfunction "C_C") (pintype "passive"))
      (node (ref "IC4") (pin "2") (pinfunction "-IN_2") (pintype "input"))
      (node (ref "R31") (pin "2") (pinfunction "2_2") (pintype "passive"))
      (node (ref "R32") (pin "1") (pinfunction "1_1") (pintype "passive"))
    )
    (net (code "38") (name "Net-(IC4A-OUT)") (class "Default")
      (node (ref "C5") (pin "2") (pinfunction "2_2") (pintype "passive"))
      (node (ref "IC4") (pin "1") (pinfunction "OUT_1") (pintype "output"))
      (node (ref "R31") (pin "1") (pinfunction "1_1") (pintype "passive"))
      (node (ref "R33") (pin "1") (pinfunction "1_1") (pintype "passive"))
    )
    (net (code "39") (name "Net-(IC4B-+IN)") (class "Default")
      (node (ref "IC4") (pin "5") (pinfunction "+IN_5") (pintype "input"))
      (node (ref "R62") (pin "1") (pinfunction "1_1") (pintype "passive"))
    )
    (net (code "40") (name "Net-(IC4B--IN)") (class "Default")
      (node (ref "D14") (pin "C") (pinfunction "C_C") (pintype "passive"))
      (node (ref "D9") (pin "A") (pinfunction "A_A") (pintype "passive"))
      (node (ref "IC4") (pin "6") (pinfunction "-IN_6") (pintype "input"))
      (node (ref "R63") (pin "2") (pinfunction "2_2") (pintype "passive"))
      (node (ref "R64") (pin "1") (pinfunction "1_1") (pintype "passive"))
    )
    (net (code "41") (name "Net-(IC4B-OUT)") (class "Default")
      (node (ref "C9") (pin "2") (pinfunction "2_2") (pintype "passive"))
      (node (ref "IC4") (pin "7") (pinfunction "OUT_7") (pintype "output"))
      (node (ref "R63") (pin "1") (pinfunction "1_1") (pintype "passive"))
      (node (ref "R65") (pin "1") (pinfunction "1_1") (pintype "passive"))
    )
    (net (code "42") (name "Net-(IC6A--IN)") (class "Default")
      (node (ref "D8") (pin "C") (pinfunction "C_C") (pintype "passive"))
      (node (ref "IC6") (pin "2") (pinfunction "-IN_2") (pintype "input"))
      (node (ref "R59") (pin "1") (pinfunction "1_1") (pintype "passive"))
      (node (ref "RS2") (pin "1") (pinfunction "1_1") (pintype "passive"))
    )
    (net (code "43") (name "Net-(IC6A-OUT)") (class "Default")
      (node (ref "D8") (pin "A") (pinfunction "A_A") (pintype "passive"))
      (node (ref "IC6") (pin "1") (pinfunction "OUT_1") (pintype "output"))
      (node (ref "Q6") (pin "1") (pinfunction "B_1") (pintype "passive"))
    )
    (net (code "44") (name "Net-(IC6B--IN)") (class "Default")
      (node (ref "C12") (pin "1") (pinfunction "1_1") (pintype "passive"))
      (node (ref "IC6") (pin "6") (pinfunction "-IN_6") (pintype "input"))
      (node (ref "Q4") (pin "3") (pinfunction "C_3") (pintype "passive"))
      (node (ref "R50") (pin "2") (pinfunction "2_2") (pintype "passive"))
    )
    (net (code "45") (name "Net-(IC6B-OUT)") (class "Default")
      (node (ref "C12") (pin "2") (pinfunction "2_2") (pintype "passive"))
      (node (ref "IC6") (pin "7") (pinfunction "OUT_7") (pintype "output"))
      (node (ref "R51") (pin "2") (pinfunction "2_2") (pintype "passive"))
    )
    (net (code "46") (name "Net-(IC7A-+IN)") (class "Default")
      (node (ref "IC7") (pin "3") (pinfunction "+IN_3") (pintype "input"))
      (node (ref "R38") (pin "2") (pinfunction "2_2") (pintype "passive"))
      (node (ref "R41") (pin "2") (pinfunction "2_2") (pintype "passive"))
    )
    (net (code "47") (name "Net-(IC7A--IN)") (class "Default")
      (node (ref "IC7") (pin "4") (pinfunction "-IN_4") (pintype "input"))
      (node (ref "R42") (pin "2") (pinfunction "2_2") (pintype "passive"))
      (node (ref "R43") (pin "1") (pinfunction "1_1") (pintype "passive"))
    )
    (net (code "48") (name "Net-(IC7A-AMP{slash}BIAS)") (class "Default")
      (node (ref "IC7") (pin "1") (pinfunction "AMP/BIAS_1") (pintype "passive"))
      (node (ref "IC7") (pin "16") (pinfunction "AMP/BIAS_16") (pintype "passive"))
      (node (ref "R52") (pin "2") (pinfunction "2_2") (pintype "passive"))
    )
    (net (code "49") (name "Net-(IC7A-BUFF{slash}IN)") (class "Default")
      (node (ref "C10") (pin "1") (pinfunction "1_1") (pintype "passive"))
      (node (ref "IC7") (pin "5") (pinfunction "OUT_5") (pintype "output"))
      (node (ref "IC7") (pin "7") (pinfunction "BUFF/IN_7") (pintype "input"))
    )
    (net (code "50") (name "Net-(IC7B-+IN)") (class "Default")
      (node (ref "I2") (pin "1") (pinfunction "1_1") (pintype "passive"))
      (node (ref "IC7") (pin "14") (pinfunction "+IN_14") (pintype "input"))
    )
    (net (code "51") (name "Net-(IC7B--IN)") (class "Default")
      (node (ref "IC7") (pin "13") (pinfunction "-IN_13") (pintype "input"))
      (node (ref "R37") (pin "2") (pinfunction "2_2") (pintype "passive"))
      (node (ref "R40") (pin "1") (pinfunction "1_1") (pintype "passive"))
    )
    (net (code "52") (name "Net-(IC7B-BUFF{slash}IN)") (class "Default")
      (node (ref "C9") (pin "1") (pinfunction "1_1") (pintype "passive"))
      (node (ref "IC7") (pin "10") (pinfunction "BUFF/IN_10") (pintype "input"))
      (node (ref "IC7") (pin "12") (pinfunction "OUT_12") (pintype "output"))
    )
    (net (code "53") (name "Net-(IC7B-BUFF{slash}OUT)") (class "Default")
      (node (ref "IC7") (pin "9") (pinfunction "BUFF/OUT_9") (pintype "output"))
      (node (ref "R38") (pin "1") (pinfunction "1_1") (pintype "passive"))
      (node (ref "R39") (pin "2") (pinfunction "2_2") (pintype "passive"))
      (node (ref "R40") (pin "2") (pinfunction "2_2") (pintype "passive"))
    )
    (net (code "54") (name "Net-(JP1-Pad1)") (class "Default")
      (node (ref "JP1") (pin "1") (pinfunction "1_1") (pintype "passive"))
      (node (ref "JP1") (pin "2") (pinfunction "2_2") (pintype "passive"))
      (node (ref "R2") (pin "1") (pinfunction "1_1") (pintype "passive"))
    )
    (net (code "55") (name "Net-(JP1-Pad10)") (class "Default")
      (node (ref "JP1") (pin "10") (pinfunction "10_10") (pintype "passive"))
      (node (ref "JP1") (pin "9") (pinfunction "9_9") (pintype "passive"))
      (node (ref "R1") (pin "1") (pinfunction "1_1") (pintype "passive"))
    )
    (net (code "56") (name "Net-(Q1-B)") (class "Default")
      (node (ref "F1") (pin "1") (pinfunction "1_1") (pintype "passive"))
      (node (ref "Q1") (pin "1") (pinfunction "B_1") (pintype "passive"))
      (node (ref "R17") (pin "2") (pinfunction "2_2") (pintype "passive"))
    )
    (net (code "57") (name "Net-(Q1-E)") (class "Default")
      (node (ref "Q1") (pin "2") (pinfunction "E_2") (pintype "passive"))
      (node (ref "Q2") (pin "2") (pinfunction "E_2") (pintype "passive"))
      (node (ref "R19") (pin "1") (pinfunction "1_1") (pintype "passive"))
    )
    (net (code "58") (name "Net-(Q2-C)") (class "Default")
      (node (ref "Q2") (pin "3") (pinfunction "C_3") (pintype "passive"))
      (node (ref "R20") (pin "1") (pinfunction "1_1") (pintype "passive"))
    )
    (net (code "59") (name "Net-(Q3-E)") (class "Default")
      (node (ref "Q3") (pin "2") (pinfunction "E_2") (pintype "passive"))
      (node (ref "R25") (pin "2") (pinfunction "2_2") (pintype "passive"))
      (node (ref "R28") (pin "2") (pinfunction "2_2") (pintype "passive"))
    )
    (net (code "60") (name "Net-(Q4-B)") (class "Default")
      (node (ref "F2") (pin "1") (pinfunction "1_1") (pintype "passive"))
      (node (ref "Q4") (pin "1") (pinfunction "B_1") (pintype "passive"))
      (node (ref "R49") (pin "2") (pinfunction "2_2") (pintype "passive"))
    )
    (net (code "61") (name "Net-(Q4-E)") (class "Default")
      (node (ref "Q4") (pin "2") (pinfunction "E_2") (pintype "passive"))
      (node (ref "Q5") (pin "2") (pinfunction "E_2") (pintype "passive"))
      (node (ref "R51") (pin "1") (pinfunction "1_1") (pintype "passive"))
    )
    (net (code "62") (name "Net-(Q5-C)") (class "Default")
      (node (ref "Q5") (pin "3") (pinfunction "C_3") (pintype "passive"))
      (node (ref "R52") (pin "1") (pinfunction "1_1") (pintype "passive"))
    )
    (net (code "63") (name "Net-(Q6-E)") (class "Default")
      (node (ref "Q6") (pin "2") (pinfunction "E_2") (pintype "passive"))
      (node (ref "R59") (pin "2") (pinfunction "2_2") (pintype "passive"))
      (node (ref "R60") (pin "2") (pinfunction "2_2") (pintype "passive"))
    )
    (net (code "64") (name "V+") (class "Default")
      (node (ref "+") (pin "1") (pinfunction "1_1") (pintype "passive"))
      (node (ref "C1") (pin "1") (pinfunction "+_1") (pintype "passive"))
      (node (ref "C13") (pin "1") (pinfunction "1_1") (pintype "passive"))
      (node (ref "C15") (pin "1") (pinfunction "1_1") (pintype "passive"))
      (node (ref "C17") (pin "1") (pinfunction "1_1") (pintype "passive"))
      (node (ref "C19") (pin "1") (pinfunction "1_1") (pintype "passive"))
      (node (ref "C21") (pin "1") (pinfunction "1_1") (pintype "passive"))
      (node (ref "C3") (pin "1") (pinfunction "1_1") (pintype "passive"))
      (node (ref "IC1") (pin "11") (pinfunction "V+_11") (pintype "power_in"))
      (node (ref "IC3") (pin "11") (pinfunction "V+_11") (pintype "power_in"))
      (node (ref "IC7") (pin "11") (pinfunction "V+_11") (pintype "power_in"))
      (node (ref "R1") (pin "2") (pinfunction "2_2") (pintype "passive"))
    )
    (net (code "65") (name "V-") (class "Default")
      (node (ref "-") (pin "1") (pinfunction "1_1") (pintype "passive"))
      (node (ref "C14") (pin "2") (pinfunction "2_2") (pintype "passive"))
      (node (ref "C16") (pin "2") (pinfunction "2_2") (pintype "passive"))
      (node (ref "C18") (pin "2") (pinfunction "2_2") (pintype "passive"))
      (node (ref "C2") (pin "2") (pinfunction "-_2") (pintype "passive"))
      (node (ref "C20") (pin "2") (pinfunction "2_2") (pintype "passive"))
      (node (ref "C22") (pin "2") (pinfunction "2_2") (pintype "passive"))
      (node (ref "C4") (pin "2") (pinfunction "2_2") (pintype "passive"))
      (node (ref "IC1") (pin "6") (pinfunction "V-_6") (pintype "power_in"))
      (node (ref "IC3") (pin "6") (pinfunction "V-_6") (pintype "power_in"))
      (node (ref "IC7") (pin "6") (pinfunction "V-_6") (pintype "power_in"))
      (node (ref "R12") (pin "1") (pinfunction "1_1") (pintype "passive"))
      (node (ref "R18") (pin "1") (pinfunction "1_1") (pintype "passive"))
      (node (ref "R2") (pin "2") (pinfunction "2_2") (pintype "passive"))
      (node (ref "R39") (pin "1") (pinfunction "1_1") (pintype "passive"))
      (node (ref "R44") (pin "1") (pinfunction "1_1") (pintype "passive"))
      (node (ref "R50") (pin "1") (pinfunction "1_1") (pintype "passive"))
      (node (ref "R7") (pin "1") (pinfunction "1_1") (pintype "passive"))
    )
    (net (code "66") (name "unconnected-(IC1A-DIODE{slash}BIAS-Pad2)") (class "Default")
      (node (ref "IC1") (pin "2") (pinfunction "DIODE/BIAS_2") (pintype "passive"))
    )
    (net (code "67") (name "unconnected-(IC1B-DIODE{slash}BIAS-Pad15)") (class "Default")
      (node (ref "IC1") (pin "15") (pinfunction "DIODE/BIAS_15") (pintype "passive"))
    )
    (net (code "68") (name "unconnected-(IC3A-BUFF{slash}IN-Pad7)") (class "Default")
      (node (ref "IC3") (pin "7") (pinfunction "BUFF/IN_7") (pintype "input"))
    )
    (net (code "69") (name "unconnected-(IC3A-BUFF{slash}OUT-Pad8)") (class "Default")
      (node (ref "IC3") (pin "8") (pinfunction "BUFF/OUT_8") (pintype "output"))
    )
    (net (code "70") (name "unconnected-(IC3A-DIODE{slash}BIAS-Pad2)") (class "Default")
      (node (ref "IC3") (pin "2") (pinfunction "DIODE/BIAS_2") (pintype "passive"))
    )
    (net (code "71") (name "unconnected-(IC3B-BUFF{slash}IN-Pad10)") (class "Default")
      (node (ref "IC3") (pin "10") (pinfunction "BUFF/IN_10") (pintype "input"))
    )
    (net (code "72") (name "unconnected-(IC3B-BUFF{slash}OUT-Pad9)") (class "Default")
      (node (ref "IC3") (pin "9") (pinfunction "BUFF/OUT_9") (pintype "output"))
    )
    (net (code "73") (name "unconnected-(IC3B-DIODE{slash}BIAS-Pad15)") (class "Default")
      (node (ref "IC3") (pin "15") (pinfunction "DIODE/BIAS_15") (pintype "passive"))
    )
    (net (code "74") (name "unconnected-(IC7A-DIODE{slash}BIAS-Pad2)") (class "Default")
      (node (ref "IC7") (pin "2") (pinfunction "DIODE/BIAS_2") (pintype "passive"))
    )
    (net (code "75") (name "unconnected-(IC7B-DIODE{slash}BIAS-Pad15)") (class "Default")
      (node (ref "IC7") (pin "15") (pinfunction "DIODE/BIAS_15") (pintype "passive"))
    )
  )
)
